# Battery_Monitor.net
KiCad netlist of a schematic drawn in EAGLE
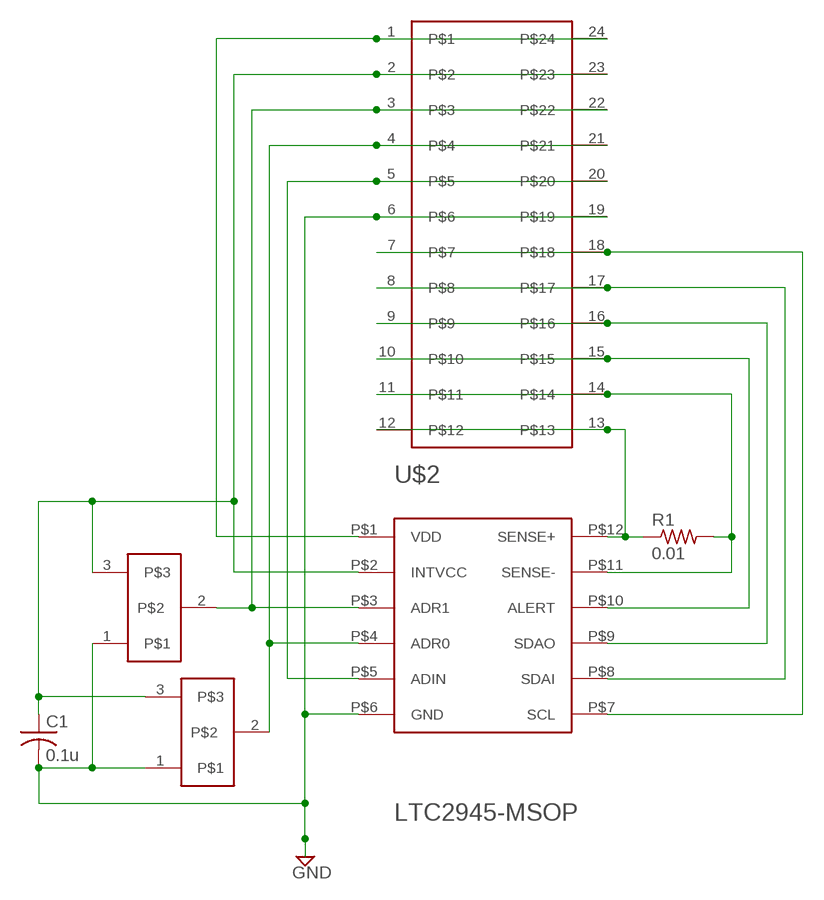
[diagram p0: schematic, sheet 1]

(export (version "E")
  (design (tool "Eeschema 10.0.6"))
  (components
    (comp (ref "C1")
      (value "0.1u")
      (footprint "eagle-import:C1812")
      (libsource (lib "eagle-import") (part "C-USC1812"))
    )
    (comp (ref "R1")
      (value "0.01")
      (footprint "eagle-import:R2010")
      (libsource (lib "eagle-import") (part "R-US_R2010"))
    )
    (comp (ref "U$2")
      (value "LTC2945-MSOP")
      (footprint "eagle-import:MSOP12")
      (libsource (lib "eagle-import") (part "LTC2945-MSOP"))
    )
    (comp (ref "U$3")
      (value "24-PINEVAL")
      (footprint "eagle-import:DIL24-6")
      (libsource (lib "eagle-import") (part "24-PINEVAL"))
    )
    (comp (ref "U$4")
      (value "JUMP-3")
      (footprint "eagle-import:JUMP-3")
      (libsource (lib "eagle-import") (part "JUMP-3"))
    )
    (comp (ref "U$5")
      (value "JUMP-3")
      (footprint "eagle-import:JUMP-3")
      (libsource (lib "eagle-import") (part "JUMP-3"))
    )
  )
  (nets
    (net (code "1") (name "GND") (class "Default")
      (node (ref "C1") (pin "2") (pinfunction "2_2") (pintype "passive"))
      (node (ref "U$2") (pin "P$6") (pinfunction "GND_P$6") (pintype "bidirectional"))
      (node (ref "U$3") (pin "19") (pinfunction "P$19_19") (pintype "bidirectional"))
      (node (ref "U$3") (pin "6") (pinfunction "P$6_6") (pintype "bidirectional"))
      (node (ref "U$4") (pin "1") (pinfunction "P$1_1") (pintype "bidirectional"))
      (node (ref "U$5") (pin "1") (pinfunction "P$1_1") (pintype "bidirectional"))
    )
    (net (code "2") (name "Net-(U$2-ADIN)") (class "Default")
      (node (ref "U$2") (pin "P$5") (pinfunction "ADIN_P$5") (pintype "bidirectional"))
      (node (ref "U$3") (pin "20") (pinfunction "P$20_20") (pintype "bidirectional"))
      (node (ref "U$3") (pin "5") (pinfunction "P$5_5") (pintype "bidirectional"))
    )
    (net (code "3") (name "Net-(U$2-ADR0)") (class "Default")
      (node (ref "U$2") (pin "P$4") (pinfunction "ADR0_P$4") (pintype "bidirectional"))
      (node (ref "U$3") (pin "21") (pinfunction "P$21_21") (pintype "bidirectional"))
      (node (ref "U$3") (pin "4") (pinfunction "P$4_4") (pintype "bidirectional"))
      (node (ref "U$5") (pin "2") (pinfunction "P$2_2") (pintype "bidirectional"))
    )
    (net (code "4") (name "Net-(U$2-ADR1)") (class "Default")
      (node (ref "U$2") (pin "P$3") (pinfunction "ADR1_P$3") (pintype "bidirectional"))
      (node (ref "U$3") (pin "22") (pinfunction "P$22_22") (pintype "bidirectional"))
      (node (ref "U$3") (pin "3") (pinfunction "P$3_3") (pintype "bidirectional"))
      (node (ref "U$4") (pin "2") (pinfunction "P$2_2") (pintype "bidirectional"))
    )
    (net (code "5") (name "Net-(U$2-ALERT)") (class "Default")
      (node (ref "U$2") (pin "P$10") (pinfunction "ALERT_P$10") (pintype "bidirectional"))
      (node (ref "U$3") (pin "10") (pinfunction "P$10_10") (pintype "bidirectional"))
      (node (ref "U$3") (pin "15") (pinfunction "P$15_15") (pintype "bidirectional"))
    )
    (net (code "6") (name "Net-(U$2-INTVCC)") (class "Default")
      (node (ref "C1") (pin "1") (pinfunction "1_1") (pintype "passive"))
      (node (ref "U$2") (pin "P$2") (pinfunction "INTVCC_P$2") (pintype "bidirectional"))
      (node (ref "U$3") (pin "2") (pinfunction "P$2_2") (pintype "bidirectional"))
      (node (ref "U$3") (pin "23") (pinfunction "P$23_23") (pintype "bidirectional"))
      (node (ref "U$4") (pin "3") (pinfunction "P$3_3") (pintype "bidirectional"))
      (node (ref "U$5") (pin "3") (pinfunction "P$3_3") (pintype "bidirectional"))
    )
    (net (code "7") (name "Net-(U$2-SCL)") (class "Default")
      (node (ref "U$2") (pin "P$7") (pinfunction "SCL_P$7") (pintype "bidirectional"))
      (node (ref "U$3") (pin "18") (pinfunction "P$18_18") (pintype "bidirectional"))
      (node (ref "U$3") (pin "7") (pinfunction "P$7_7") (pintype "bidirectional"))
    )
    (net (code "8") (name "Net-(U$2-SDAI)") (class "Default")
      (node (ref "U$2") (pin "P$8") (pinfunction "SDAI_P$8") (pintype "bidirectional"))
      (node (ref "U$3") (pin "17") (pinfunction "P$17_17") (pintype "bidirectional"))
      (node (ref "U$3") (pin "8") (pinfunction "P$8_8") (pintype "bidirectional"))
    )
    (net (code "9") (name "Net-(U$2-SDAO)") (class "Default")
      (node (ref "U$2") (pin "P$9") (pinfunction "SDAO_P$9") (pintype "bidirectional"))
      (node (ref "U$3") (pin "16") (pinfunction "P$16_16") (pintype "bidirectional"))
      (node (ref "U$3") (pin "9") (pinfunction "P$9_9") (pintype "bidirectional"))
    )
    (net (code "10") (name "Net-(U$2-SENSE+)") (class "Default")
      (node (ref "R1") (pin "1") (pinfunction "1_1") (pintype "passive"))
      (node (ref "U$2") (pin "P$12") (pinfunction "SENSE+_P$12") (pintype "bidirectional"))
      (node (ref "U$3") (pin "12") (pinfunction "P$12_12") (pintype "bidirectional"))
      (node (ref "U$3") (pin "13") (pinfunction "P$13_13") (pintype "bidirectional"))
    )
    (net (code "11") (name "Net-(U$2-SENSE-)") (class "Default")
      (node (ref "R1") (pin "2") (pinfunction "2_2") (pintype "passive"))
      (node (ref "U$2") (pin "P$11") (pinfunction "SENSE-_P$11") (pintype "bidirectional"))
      (node (ref "U$3") (pin "11") (pinfunction "P$11_11") (pintype "bidirectional"))
      (node (ref "U$3") (pin "14") (pinfunction "P$14_14") (pintype "bidirectional"))
    )
    (net (code "12") (name "Net-(U$2-VDD)") (class "Default")
      (node (ref "U$2") (pin "P$1") (pinfunction "VDD_P$1") (pintype "bidirectional"))
      (node (ref "U$3") (pin "1") (pinfunction "P$1_1") (pintype "bidirectional"))
      (node (ref "U$3") (pin "24") (pinfunction "P$24_24") (pintype "bidirectional"))
    )
  )
)
